# zamekKodowy_nadajnik.net
KiCad netlist of a schematic drawn in EAGLE
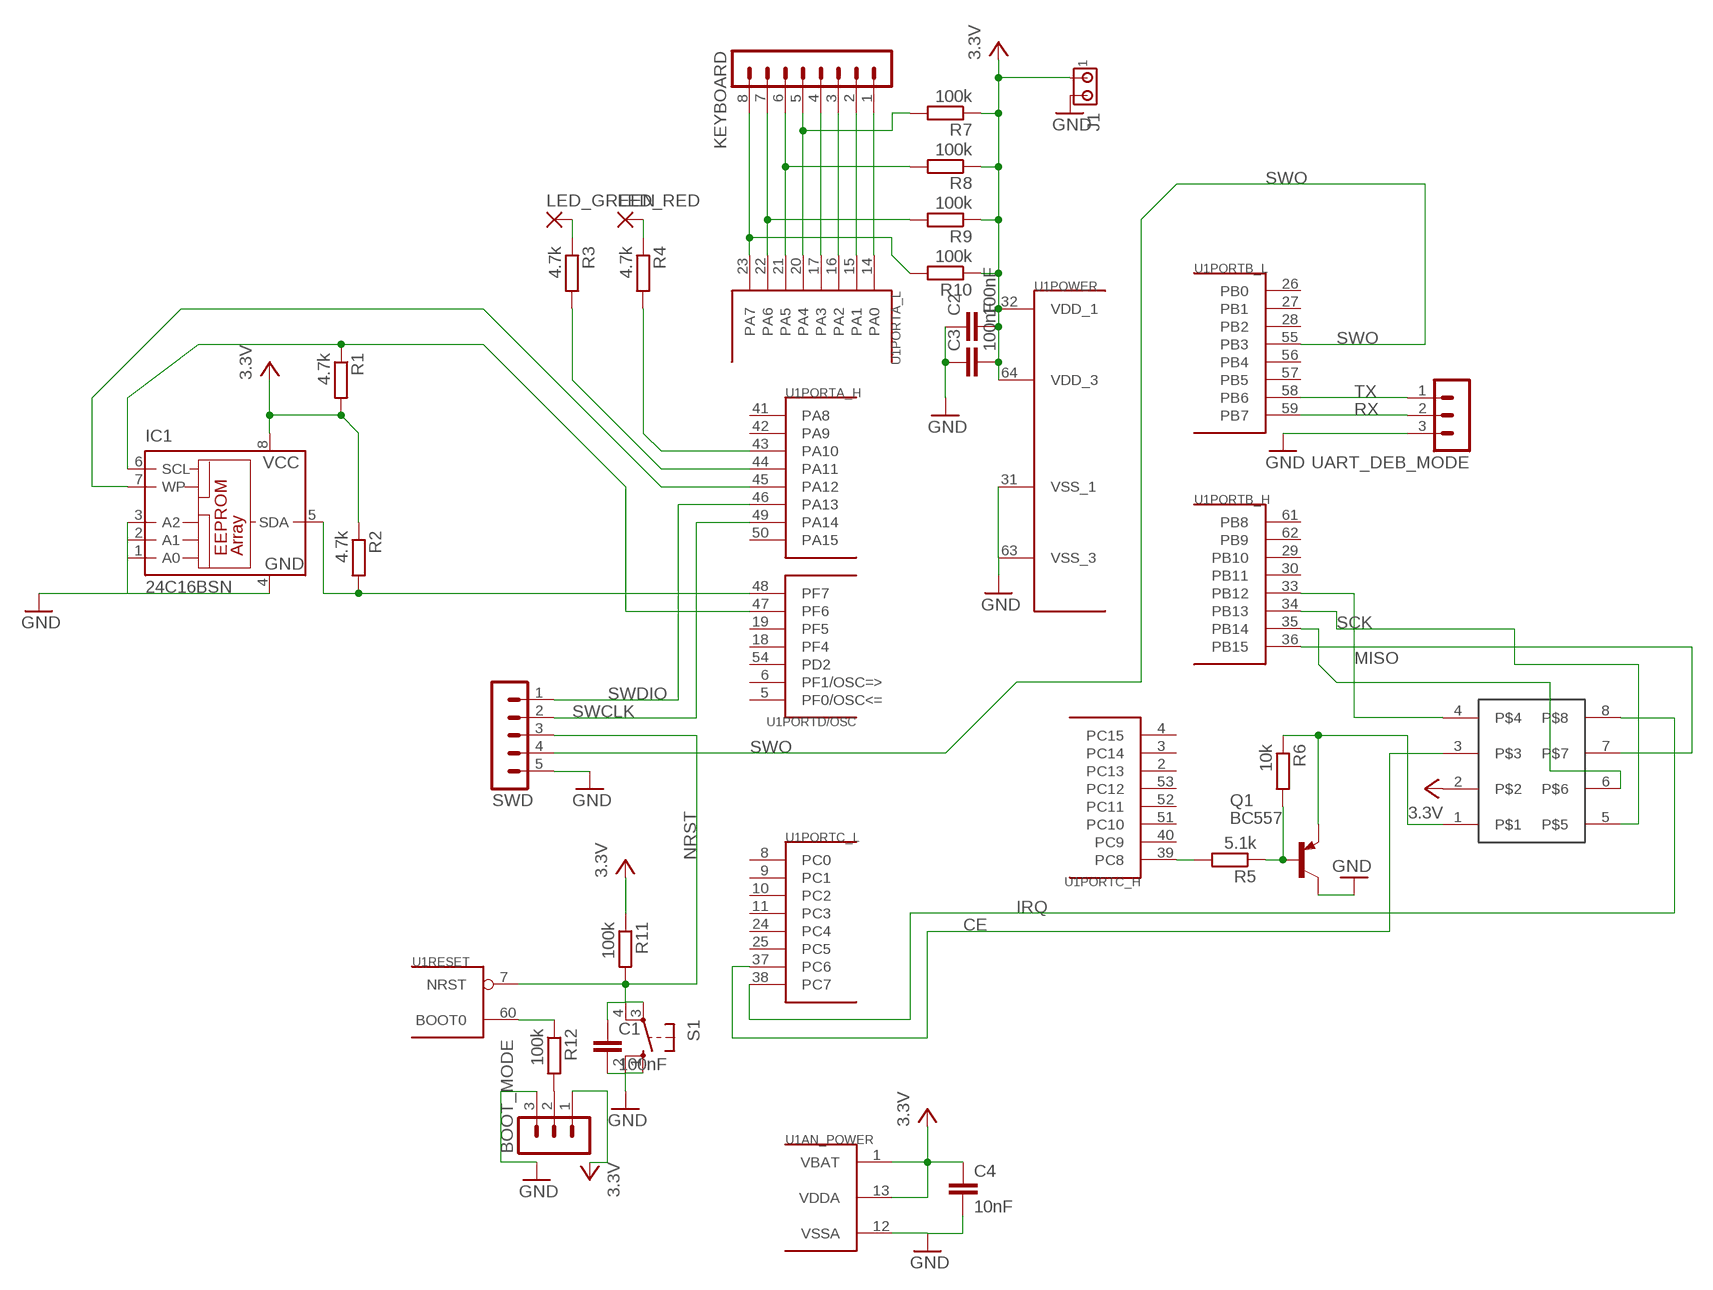
[diagram p0: schematic, sheet 1]

(export (version "E")
  (design (tool "Eeschema 10.0.6"))
  (components
    (comp (ref "BOOT_MODE")
      (value "MA03-1")
      (footprint "eagle-import:MA03-1")
      (fields (field (name "OC_FARNELL") "unknown") (field (name "OC_NEWARK") "unknown"))
      (libsource (lib "eagle-import") (part "MA03-1"))
    )
    (comp (ref "C1")
      (value "100nF")
      (footprint "eagle-import:C0603")
      (libsource (lib "eagle-import") (part "C-EUC0603"))
    )
    (comp (ref "C2")
      (value "100nF")
      (footprint "eagle-import:C0603")
      (libsource (lib "eagle-import") (part "C-EUC0603"))
    )
    (comp (ref "C3")
      (value "100nF")
      (footprint "eagle-import:C0603")
      (libsource (lib "eagle-import") (part "C-EUC0603"))
    )
    (comp (ref "C4")
      (value "10nF")
      (footprint "eagle-import:C0603")
      (libsource (lib "eagle-import") (part "C-EUC0603"))
    )
    (comp (ref "CON1")
      (value "CON10")
      (footprint "eagle-import:CON10")
      (libsource (lib "eagle-import") (part "CON10"))
    )
    (comp (ref "IC1")
      (value "24C16BSN")
      (footprint "eagle-import:SO-08")
      (fields (field (name "MPN") "AT24C16BN-SH-B"))
      (libsource (lib "eagle-import") (part "24SNC16B"))
    )
    (comp (ref "J1")
      (value "MTA02-100")
      (footprint "eagle-import:10X02MTA")
      (libsource (lib "eagle-import") (part "MTA02-100"))
    )
    (comp (ref "KEYBOARD")
      (value "MA08-1")
      (footprint "eagle-import:MA08-1")
      (libsource (lib "eagle-import") (part "MA08-1"))
    )
    (comp (ref "LED_GREEN")
      (value "2,54/0,9")
      (footprint "eagle-import:2,54_0,9")
      (libsource (lib "eagle-import") (part "2,54/0,9"))
    )
    (comp (ref "LED_RED")
      (value "2,54/0,9")
      (footprint "eagle-import:2,54_0,9")
      (libsource (lib "eagle-import") (part "2,54/0,9"))
    )
    (comp (ref "Q1")
      (value "BC557")
      (footprint "eagle-import:TO92")
      (libsource (lib "eagle-import") (part "BC557"))
    )
    (comp (ref "R1")
      (value "4.7k")
      (footprint "eagle-import:R0603")
      (libsource (lib "eagle-import") (part "R-EU_R0603"))
    )
    (comp (ref "R2")
      (value "4.7k")
      (footprint "eagle-import:R0603")
      (libsource (lib "eagle-import") (part "R-EU_R0603"))
    )
    (comp (ref "R3")
      (value "4.7k")
      (footprint "eagle-import:R0603")
      (libsource (lib "eagle-import") (part "R-EU_R0603"))
    )
    (comp (ref "R4")
      (value "4.7k")
      (footprint "eagle-import:R0603")
      (libsource (lib "eagle-import") (part "R-EU_R0603"))
    )
    (comp (ref "R5")
      (value "5.1k")
      (footprint "eagle-import:R0603")
      (libsource (lib "eagle-import") (part "R-EU_R0603"))
    )
    (comp (ref "R6")
      (value "10k")
      (footprint "eagle-import:R0603")
      (libsource (lib "eagle-import") (part "R-EU_R0603"))
    )
    (comp (ref "R7")
      (value "100k")
      (footprint "eagle-import:R0603")
      (libsource (lib "eagle-import") (part "R-EU_R0603"))
    )
    (comp (ref "R8")
      (value "100k")
      (footprint "eagle-import:R0603")
      (libsource (lib "eagle-import") (part "R-EU_R0603"))
    )
    (comp (ref "R9")
      (value "100k")
      (footprint "eagle-import:R0603")
      (libsource (lib "eagle-import") (part "R-EU_R0603"))
    )
    (comp (ref "R10")
      (value "100k")
      (footprint "eagle-import:R0603")
      (libsource (lib "eagle-import") (part "R-EU_R0603"))
    )
    (comp (ref "R11")
      (value "100k")
      (footprint "eagle-import:R0603")
      (libsource (lib "eagle-import") (part "R-EU_R0603"))
    )
    (comp (ref "R12")
      (value "100k")
      (footprint "eagle-import:R0603")
      (libsource (lib "eagle-import") (part "R-EU_R0603"))
    )
    (comp (ref "S1")
      (value "10-XX")
      (footprint "eagle-import:B3F-10XX")
      (fields (field (name "MPN") "B3F-1000"))
      (libsource (lib "eagle-import") (part "10-XX"))
    )
    (comp (ref "SWD")
      (value "MA05-1")
      (footprint "eagle-import:MA05-1")
      (libsource (lib "eagle-import") (part "MA05-1"))
    )
    (comp (ref "U1")
      (value "STM32F10XRXT6")
      (footprint "eagle-import:TQFP64")
      (libsource (lib "eagle-import") (part "STM32F10XRXT6"))
    )
    (comp (ref "UART_DEB_MODE")
      (value "MA03-1")
      (footprint "eagle-import:MA03-1")
      (libsource (lib "eagle-import") (part "MA03-1"))
    )
  )
  (nets
    (net (code "1") (name "/CE") (class "Default")
      (node (ref "CON1") (pin "3") (pinfunction "P$3_3") (pintype "bidirectional"))
      (node (ref "U1") (pin "37") (pinfunction "PC6_37") (pintype "bidirectional"))
    )
    (net (code "2") (name "/IRQ") (class "Default")
      (node (ref "CON1") (pin "8") (pinfunction "P$8_8") (pintype "bidirectional"))
      (node (ref "U1") (pin "38") (pinfunction "PC7_38") (pintype "bidirectional"))
    )
    (net (code "3") (name "/MISO") (class "Default")
      (node (ref "CON1") (pin "7") (pinfunction "P$7_7") (pintype "bidirectional"))
      (node (ref "U1") (pin "36") (pinfunction "PB15_36") (pintype "bidirectional"))
    )
    (net (code "4") (name "/NRST") (class "Default")
      (node (ref "C1") (pin "1") (pinfunction "1_1") (pintype "passive"))
      (node (ref "R11") (pin "2") (pinfunction "2_2") (pintype "passive"))
      (node (ref "S1") (pin "3") (pinfunction "P_3") (pintype "passive"))
      (node (ref "S1") (pin "4") (pinfunction "P1_4") (pintype "passive"))
      (node (ref "SWD") (pin "3") (pinfunction "3_3") (pintype "passive"))
      (node (ref "U1") (pin "7") (pinfunction "NRST_7") (pintype "input"))
    )
    (net (code "5") (name "/RX") (class "Default")
      (node (ref "U1") (pin "59") (pinfunction "PB7_59") (pintype "bidirectional"))
      (node (ref "UART_DEB_MODE") (pin "2") (pinfunction "2_2") (pintype "passive"))
    )
    (net (code "6") (name "/SCK") (class "Default")
      (node (ref "CON1") (pin "5") (pinfunction "P$5_5") (pintype "bidirectional"))
      (node (ref "U1") (pin "34") (pinfunction "PB13_34") (pintype "bidirectional"))
    )
    (net (code "7") (name "/SWCLK") (class "Default")
      (node (ref "SWD") (pin "2") (pinfunction "2_2") (pintype "passive"))
      (node (ref "U1") (pin "49") (pinfunction "PA14_49") (pintype "bidirectional"))
    )
    (net (code "8") (name "/SWDIO") (class "Default")
      (node (ref "SWD") (pin "1") (pinfunction "1_1") (pintype "passive"))
      (node (ref "U1") (pin "46") (pinfunction "PA13_46") (pintype "bidirectional"))
    )
    (net (code "9") (name "/SWO") (class "Default")
      (node (ref "SWD") (pin "4") (pinfunction "4_4") (pintype "passive"))
      (node (ref "U1") (pin "55") (pinfunction "PB3_55") (pintype "bidirectional"))
    )
    (net (code "10") (name "/TX") (class "Default")
      (node (ref "U1") (pin "58") (pinfunction "PB6_58") (pintype "bidirectional"))
      (node (ref "UART_DEB_MODE") (pin "1") (pinfunction "1_1") (pintype "passive"))
    )
    (net (code "11") (name "3.3V") (class "Default")
      (node (ref "BOOT_MODE") (pin "1") (pinfunction "1_1") (pintype "passive"))
      (node (ref "C2") (pin "2") (pinfunction "2_2") (pintype "passive"))
      (node (ref "C3") (pin "2") (pinfunction "2_2") (pintype "passive"))
      (node (ref "C4") (pin "1") (pinfunction "1_1") (pintype "passive"))
      (node (ref "CON1") (pin "2") (pinfunction "P$2_2") (pintype "bidirectional"))
      (node (ref "IC1") (pin "8") (pinfunction "VCC_8") (pintype "power_in"))
      (node (ref "J1") (pin "1") (pinfunction "1_1") (pintype "passive"))
      (node (ref "R1") (pin "2") (pinfunction "2_2") (pintype "passive"))
      (node (ref "R10") (pin "1") (pinfunction "1_1") (pintype "passive"))
      (node (ref "R11") (pin "1") (pinfunction "1_1") (pintype "passive"))
      (node (ref "R2") (pin "1") (pinfunction "1_1") (pintype "passive"))
      (node (ref "R7") (pin "1") (pinfunction "1_1") (pintype "passive"))
      (node (ref "R8") (pin "1") (pinfunction "1_1") (pintype "passive"))
      (node (ref "R9") (pin "1") (pinfunction "1_1") (pintype "passive"))
      (node (ref "U1") (pin "1") (pinfunction "VBAT_1") (pintype "power_in"))
      (node (ref "U1") (pin "13") (pinfunction "VDDA_13") (pintype "power_in"))
      (node (ref "U1") (pin "32") (pinfunction "VDD_1_32") (pintype "power_in"))
      (node (ref "U1") (pin "64") (pinfunction "VDD_3_64") (pintype "power_in"))
    )
    (net (code "12") (name "GND") (class "Default")
      (node (ref "BOOT_MODE") (pin "3") (pinfunction "3_3") (pintype "passive"))
      (node (ref "C1") (pin "2") (pinfunction "2_2") (pintype "passive"))
      (node (ref "C2") (pin "1") (pinfunction "1_1") (pintype "passive"))
      (node (ref "C3") (pin "1") (pinfunction "1_1") (pintype "passive"))
      (node (ref "C4") (pin "2") (pinfunction "2_2") (pintype "passive"))
      (node (ref "IC1") (pin "1") (pinfunction "A0_1") (pintype "input"))
      (node (ref "IC1") (pin "2") (pinfunction "A1_2") (pintype "input"))
      (node (ref "IC1") (pin "3") (pinfunction "A2_3") (pintype "input"))
      (node (ref "IC1") (pin "4") (pinfunction "GND_4") (pintype "power_in"))
      (node (ref "J1") (pin "2") (pinfunction "2_2") (pintype "passive"))
      (node (ref "Q1") (pin "3") (pinfunction "C_3") (pintype "passive"))
      (node (ref "S1") (pin "1") (pinfunction "S_1") (pintype "passive"))
      (node (ref "S1") (pin "2") (pinfunction "S1_2") (pintype "passive"))
      (node (ref "SWD") (pin "5") (pinfunction "5_5") (pintype "passive"))
      (node (ref "U1") (pin "12") (pinfunction "VSSA_12") (pintype "power_in"))
      (node (ref "U1") (pin "31") (pinfunction "VSS_1_31") (pintype "power_in"))
      (node (ref "U1") (pin "63") (pinfunction "VSS_3_63") (pintype "power_in"))
      (node (ref "UART_DEB_MODE") (pin "3") (pinfunction "3_3") (pintype "passive"))
    )
    (net (code "13") (name "Net-(BOOT_MODE-Pad2)") (class "Default")
      (node (ref "BOOT_MODE") (pin "2") (pinfunction "2_2") (pintype "passive"))
      (node (ref "R12") (pin "2") (pinfunction "2_2") (pintype "passive"))
    )
    (net (code "14") (name "Net-(CON1-P$1)") (class "Default")
      (node (ref "CON1") (pin "1") (pinfunction "P$1_1") (pintype "bidirectional"))
      (node (ref "Q1") (pin "1") (pinfunction "E_1") (pintype "passive"))
      (node (ref "R6") (pin "1") (pinfunction "1_1") (pintype "passive"))
    )
    (net (code "15") (name "Net-(CON1-P$4)") (class "Default")
      (node (ref "CON1") (pin "4") (pinfunction "P$4_4") (pintype "bidirectional"))
      (node (ref "U1") (pin "33") (pinfunction "PB12_33") (pintype "bidirectional"))
    )
    (net (code "16") (name "Net-(CON1-P$6)") (class "Default")
      (node (ref "CON1") (pin "6") (pinfunction "P$6_6") (pintype "bidirectional"))
      (node (ref "U1") (pin "35") (pinfunction "PB14_35") (pintype "bidirectional"))
    )
    (net (code "17") (name "Net-(IC1-SCL)") (class "Default")
      (node (ref "IC1") (pin "6") (pinfunction "SCL_6") (pintype "input"))
      (node (ref "R1") (pin "1") (pinfunction "1_1") (pintype "passive"))
      (node (ref "U1") (pin "47") (pinfunction "PF6_47") (pintype "bidirectional"))
    )
    (net (code "18") (name "Net-(IC1-SDA)") (class "Default")
      (node (ref "IC1") (pin "5") (pinfunction "SDA_5") (pintype "bidirectional"))
      (node (ref "R2") (pin "2") (pinfunction "2_2") (pintype "passive"))
      (node (ref "U1") (pin "48") (pinfunction "PF7_48") (pintype "bidirectional"))
    )
    (net (code "19") (name "Net-(IC1-WP)") (class "Default")
      (node (ref "IC1") (pin "7") (pinfunction "WP_7") (pintype "input"))
      (node (ref "U1") (pin "45") (pinfunction "PA12_45") (pintype "bidirectional"))
    )
    (net (code "20") (name "Net-(LED_GREEN-P)") (class "Default")
      (node (ref "LED_GREEN") (pin "1") (pinfunction "P_1") (pintype "passive"))
      (node (ref "R3") (pin "1") (pinfunction "1_1") (pintype "passive"))
    )
    (net (code "21") (name "Net-(LED_RED-P)") (class "Default")
      (node (ref "LED_RED") (pin "1") (pinfunction "P_1") (pintype "passive"))
      (node (ref "R4") (pin "1") (pinfunction "1_1") (pintype "passive"))
    )
    (net (code "22") (name "Net-(Q1-B)") (class "Default")
      (node (ref "Q1") (pin "2") (pinfunction "B_2") (pintype "passive"))
      (node (ref "R5") (pin "1") (pinfunction "1_1") (pintype "passive"))
      (node (ref "R6") (pin "2") (pinfunction "2_2") (pintype "passive"))
    )
    (net (code "23") (name "Net-(U1B-PA10)") (class "Default")
      (node (ref "R4") (pin "2") (pinfunction "2_2") (pintype "passive"))
      (node (ref "U1") (pin "43") (pinfunction "PA10_43") (pintype "bidirectional"))
    )
    (net (code "24") (name "Net-(U1B-PA11)") (class "Default")
      (node (ref "R3") (pin "2") (pinfunction "2_2") (pintype "passive"))
      (node (ref "U1") (pin "44") (pinfunction "PA11_44") (pintype "bidirectional"))
    )
    (net (code "25") (name "Net-(U1C-PA0)") (class "Default")
      (node (ref "KEYBOARD") (pin "1") (pinfunction "1_1") (pintype "passive"))
      (node (ref "U1") (pin "14") (pinfunction "PA0_14") (pintype "bidirectional"))
    )
    (net (code "26") (name "Net-(U1C-PA1)") (class "Default")
      (node (ref "KEYBOARD") (pin "2") (pinfunction "2_2") (pintype "passive"))
      (node (ref "U1") (pin "15") (pinfunction "PA1_15") (pintype "bidirectional"))
    )
    (net (code "27") (name "Net-(U1C-PA2)") (class "Default")
      (node (ref "KEYBOARD") (pin "3") (pinfunction "3_3") (pintype "passive"))
      (node (ref "U1") (pin "16") (pinfunction "PA2_16") (pintype "bidirectional"))
    )
    (net (code "28") (name "Net-(U1C-PA3)") (class "Default")
      (node (ref "KEYBOARD") (pin "4") (pinfunction "4_4") (pintype "passive"))
      (node (ref "U1") (pin "17") (pinfunction "PA3_17") (pintype "bidirectional"))
    )
    (net (code "29") (name "Net-(U1C-PA4)") (class "Default")
      (node (ref "KEYBOARD") (pin "5") (pinfunction "5_5") (pintype "passive"))
      (node (ref "R7") (pin "2") (pinfunction "2_2") (pintype "passive"))
      (node (ref "U1") (pin "20") (pinfunction "PA4_20") (pintype "bidirectional"))
    )
    (net (code "30") (name "Net-(U1C-PA5)") (class "Default")
      (node (ref "KEYBOARD") (pin "6") (pinfunction "6_6") (pintype "passive"))
      (node (ref "R8") (pin "2") (pinfunction "2_2") (pintype "passive"))
      (node (ref "U1") (pin "21") (pinfunction "PA5_21") (pintype "bidirectional"))
    )
    (net (code "31") (name "Net-(U1C-PA6)") (class "Default")
      (node (ref "KEYBOARD") (pin "7") (pinfunction "7_7") (pintype "passive"))
      (node (ref "R9") (pin "2") (pinfunction "2_2") (pintype "passive"))
      (node (ref "U1") (pin "22") (pinfunction "PA6_22") (pintype "bidirectional"))
    )
    (net (code "32") (name "Net-(U1C-PA7)") (class "Default")
      (node (ref "KEYBOARD") (pin "8") (pinfunction "8_8") (pintype "passive"))
      (node (ref "R10") (pin "2") (pinfunction "2_2") (pintype "passive"))
      (node (ref "U1") (pin "23") (pinfunction "PA7_23") (pintype "bidirectional"))
    )
    (net (code "33") (name "Net-(U1F-PC8)") (class "Default")
      (node (ref "R5") (pin "2") (pinfunction "2_2") (pintype "passive"))
      (node (ref "U1") (pin "39") (pinfunction "PC8_39") (pintype "bidirectional"))
    )
    (net (code "34") (name "Net-(U1J-BOOT0)") (class "Default")
      (node (ref "R12") (pin "1") (pinfunction "1_1") (pintype "passive"))
      (node (ref "U1") (pin "60") (pinfunction "BOOT0_60") (pintype "input"))
    )
    (net (code "35") (name "unconnected-(U1B-PA8-Pad41)") (class "Default")
      (node (ref "U1") (pin "41") (pinfunction "PA8_41") (pintype "bidirectional"))
    )
    (net (code "36") (name "unconnected-(U1B-PA9-Pad42)") (class "Default")
      (node (ref "U1") (pin "42") (pinfunction "PA9_42") (pintype "bidirectional"))
    )
    (net (code "37") (name "unconnected-(U1B-PA15-Pad50)") (class "Default")
      (node (ref "U1") (pin "50") (pinfunction "PA15_50") (pintype "bidirectional"))
    )
    (net (code "38") (name "unconnected-(U1D-PB8-Pad61)") (class "Default")
      (node (ref "U1") (pin "61") (pinfunction "PB8_61") (pintype "bidirectional"))
    )
    (net (code "39") (name "unconnected-(U1D-PB9-Pad62)") (class "Default")
      (node (ref "U1") (pin "62") (pinfunction "PB9_62") (pintype "bidirectional"))
    )
    (net (code "40") (name "unconnected-(U1D-PB10-Pad29)") (class "Default")
      (node (ref "U1") (pin "29") (pinfunction "PB10_29") (pintype "bidirectional"))
    )
    (net (code "41") (name "unconnected-(U1D-PB11-Pad30)") (class "Default")
      (node (ref "U1") (pin "30") (pinfunction "PB11_30") (pintype "bidirectional"))
    )
    (net (code "42") (name "unconnected-(U1E-PB0-Pad26)") (class "Default")
      (node (ref "U1") (pin "26") (pinfunction "PB0_26") (pintype "bidirectional"))
    )
    (net (code "43") (name "unconnected-(U1E-PB1-Pad27)") (class "Default")
      (node (ref "U1") (pin "27") (pinfunction "PB1_27") (pintype "bidirectional"))
    )
    (net (code "44") (name "unconnected-(U1E-PB2-Pad28)") (class "Default")
      (node (ref "U1") (pin "28") (pinfunction "PB2_28") (pintype "bidirectional"))
    )
    (net (code "45") (name "unconnected-(U1E-PB4-Pad56)") (class "Default")
      (node (ref "U1") (pin "56") (pinfunction "PB4_56") (pintype "bidirectional"))
    )
    (net (code "46") (name "unconnected-(U1E-PB5-Pad57)") (class "Default")
      (node (ref "U1") (pin "57") (pinfunction "PB5_57") (pintype "bidirectional"))
    )
    (net (code "47") (name "unconnected-(U1F-PC9-Pad40)") (class "Default")
      (node (ref "U1") (pin "40") (pinfunction "PC9_40") (pintype "bidirectional"))
    )
    (net (code "48") (name "unconnected-(U1F-PC10-Pad51)") (class "Default")
      (node (ref "U1") (pin "51") (pinfunction "PC10_51") (pintype "bidirectional"))
    )
    (net (code "49") (name "unconnected-(U1F-PC11-Pad52)") (class "Default")
      (node (ref "U1") (pin "52") (pinfunction "PC11_52") (pintype "bidirectional"))
    )
    (net (code "50") (name "unconnected-(U1F-PC12-Pad53)") (class "Default")
      (node (ref "U1") (pin "53") (pinfunction "PC12_53") (pintype "bidirectional"))
    )
    (net (code "51") (name "unconnected-(U1F-PC13-Pad2)") (class "Default")
      (node (ref "U1") (pin "2") (pinfunction "PC13_2") (pintype "bidirectional"))
    )
    (net (code "52") (name "unconnected-(U1F-PC14-Pad3)") (class "Default")
      (node (ref "U1") (pin "3") (pinfunction "PC14_3") (pintype "bidirectional"))
    )
    (net (code "53") (name "unconnected-(U1F-PC15-Pad4)") (class "Default")
      (node (ref "U1") (pin "4") (pinfunction "PC15_4") (pintype "bidirectional"))
    )
    (net (code "54") (name "unconnected-(U1G-PC0-Pad8)") (class "Default")
      (node (ref "U1") (pin "8") (pinfunction "PC0_8") (pintype "bidirectional"))
    )
    (net (code "55") (name "unconnected-(U1G-PC1-Pad9)") (class "Default")
      (node (ref "U1") (pin "9") (pinfunction "PC1_9") (pintype "bidirectional"))
    )
    (net (code "56") (name "unconnected-(U1G-PC2-Pad10)") (class "Default")
      (node (ref "U1") (pin "10") (pinfunction "PC2_10") (pintype "bidirectional"))
    )
    (net (code "57") (name "unconnected-(U1G-PC3-Pad11)") (class "Default")
      (node (ref "U1") (pin "11") (pinfunction "PC3_11") (pintype "bidirectional"))
    )
    (net (code "58") (name "unconnected-(U1G-PC4-Pad24)") (class "Default")
      (node (ref "U1") (pin "24") (pinfunction "PC4_24") (pintype "bidirectional"))
    )
    (net (code "59") (name "unconnected-(U1G-PC5-Pad25)") (class "Default")
      (node (ref "U1") (pin "25") (pinfunction "PC5_25") (pintype "bidirectional"))
    )
    (net (code "60") (name "unconnected-(U1H-PD2-Pad54)") (class "Default")
      (node (ref "U1") (pin "54") (pinfunction "PD2_54") (pintype "bidirectional"))
    )
    (net (code "61") (name "unconnected-(U1H-PF0{slash}OSC<=-Pad5)") (class "Default")
      (node (ref "U1") (pin "5") (pinfunction "PF0/OSC<=_5") (pintype "bidirectional"))
    )
    (net (code "62") (name "unconnected-(U1H-PF1{slash}OSC=>-Pad6)") (class "Default")
      (node (ref "U1") (pin "6") (pinfunction "PF1/OSC=>_6") (pintype "bidirectional"))
    )
    (net (code "63") (name "unconnected-(U1H-PF4-Pad18)") (class "Default")
      (node (ref "U1") (pin "18") (pinfunction "PF4_18") (pintype "bidirectional"))
    )
    (net (code "64") (name "unconnected-(U1H-PF5-Pad19)") (class "Default")
      (node (ref "U1") (pin "19") (pinfunction "PF5_19") (pintype "bidirectional"))
    )
  )
)
